# STM32_F407.net
KiCad netlist of a schematic drawn in Altium Designer
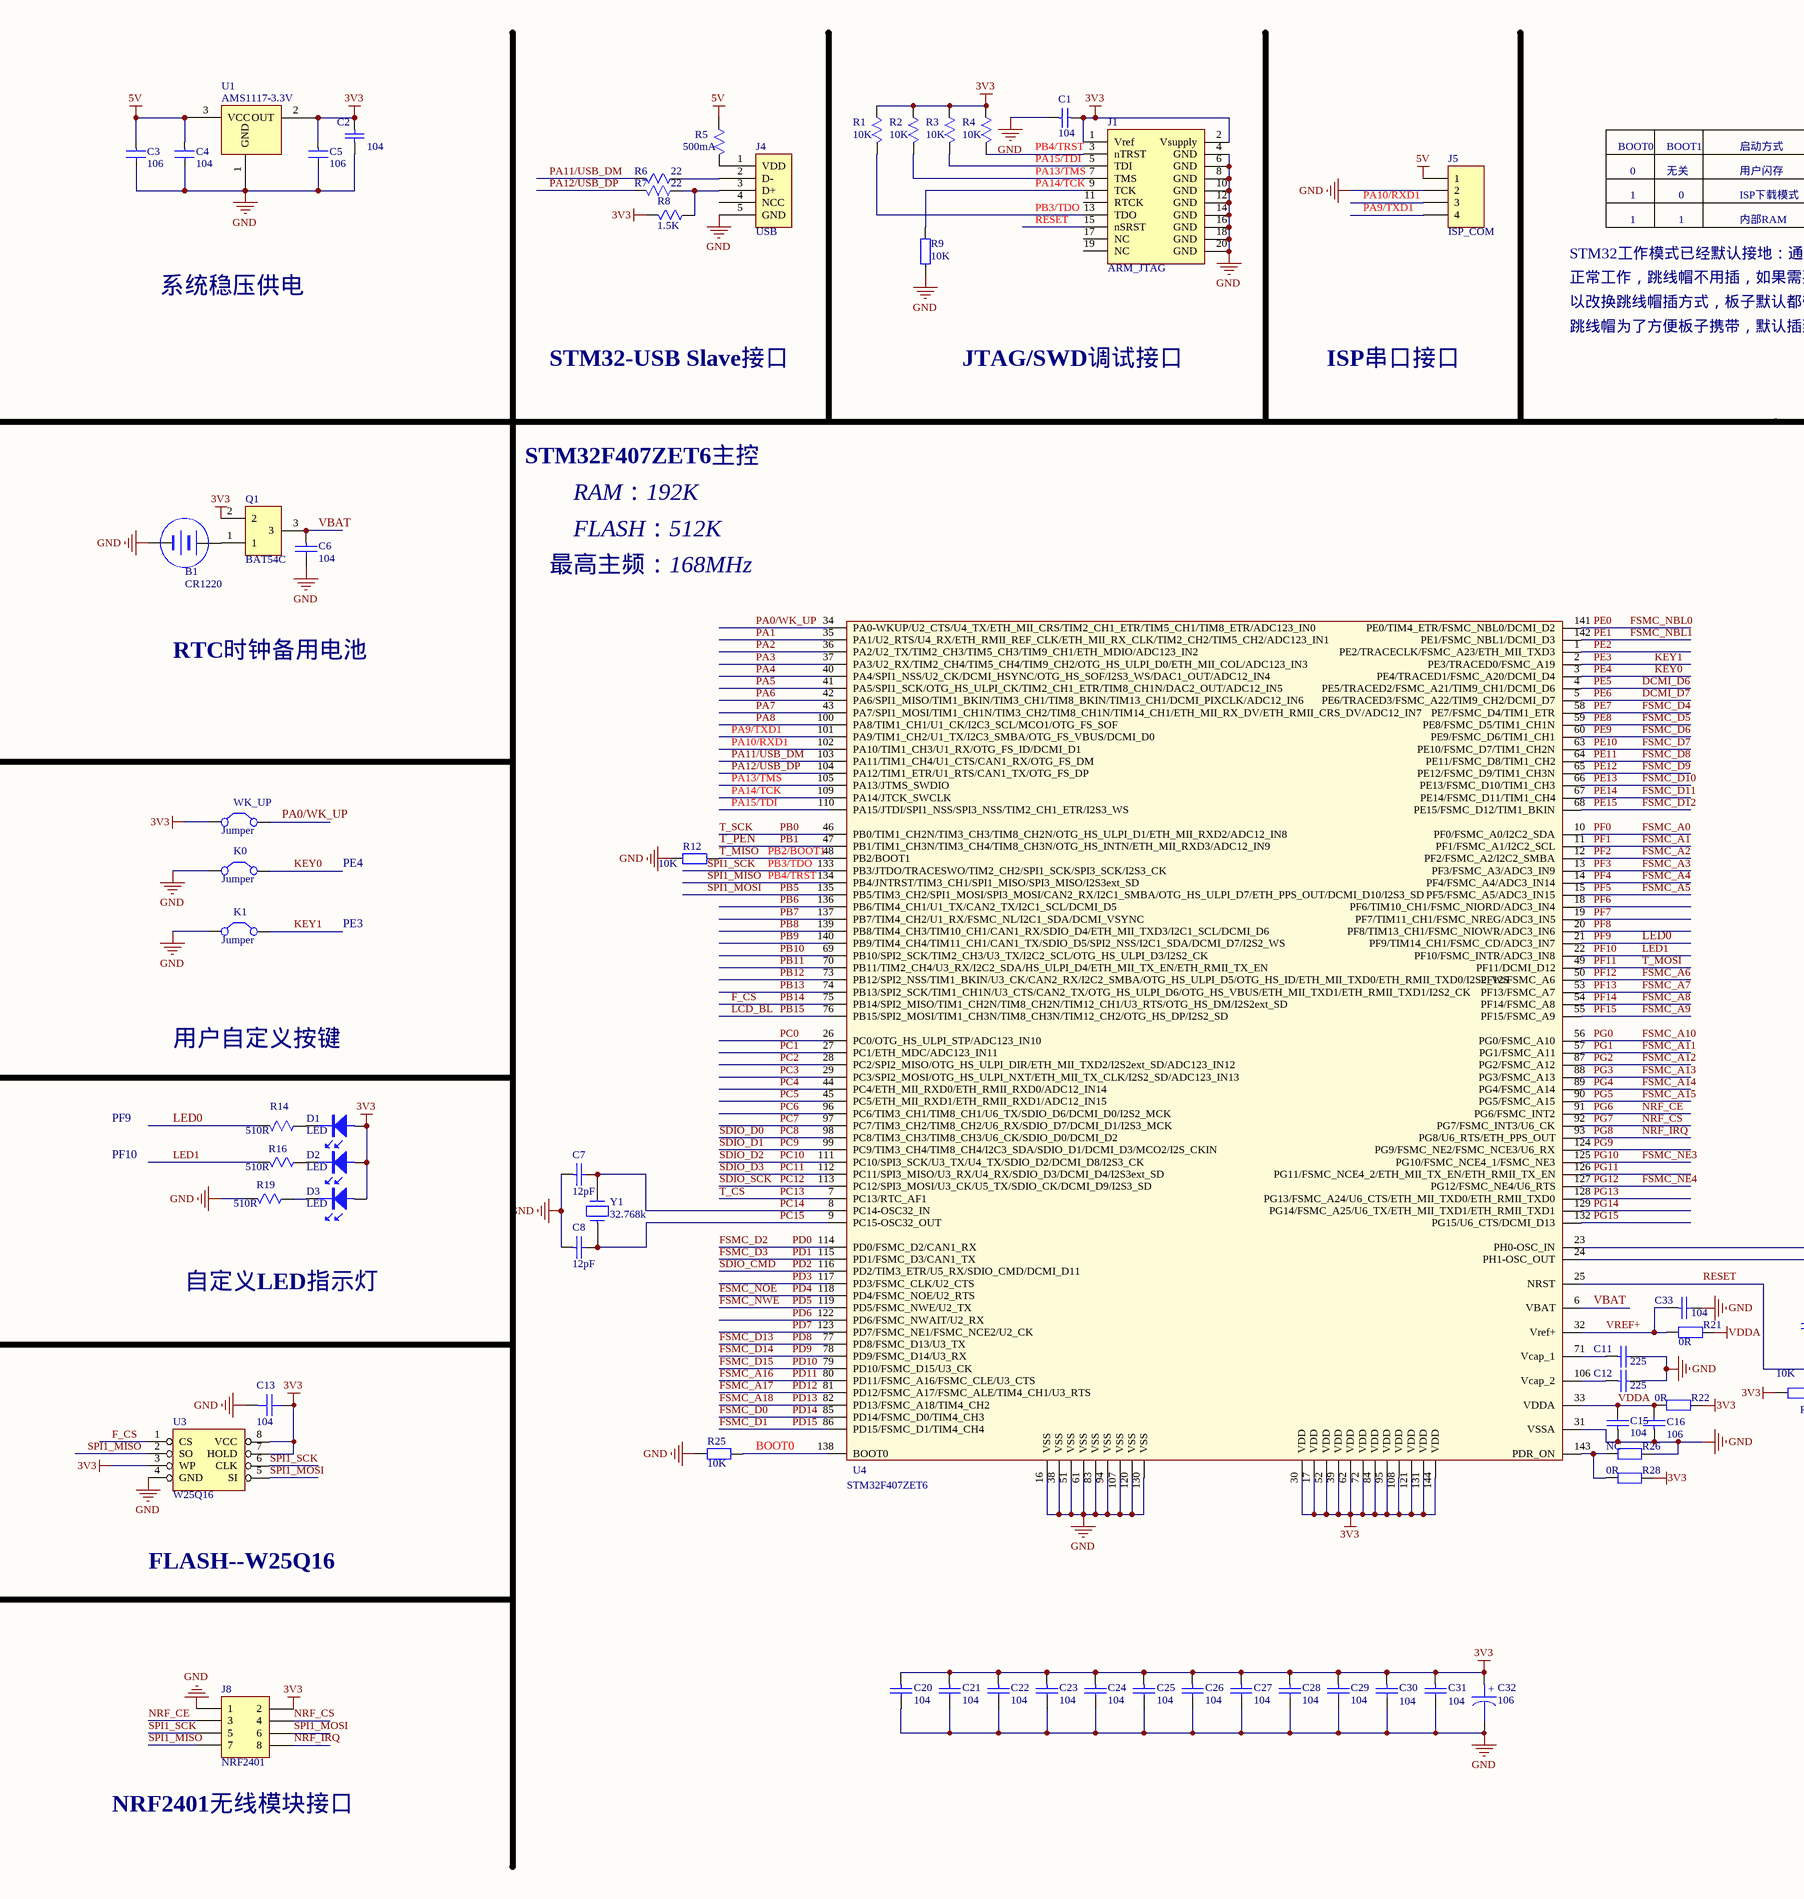
[diagram p0: STM32_F407.SchDoc, left]
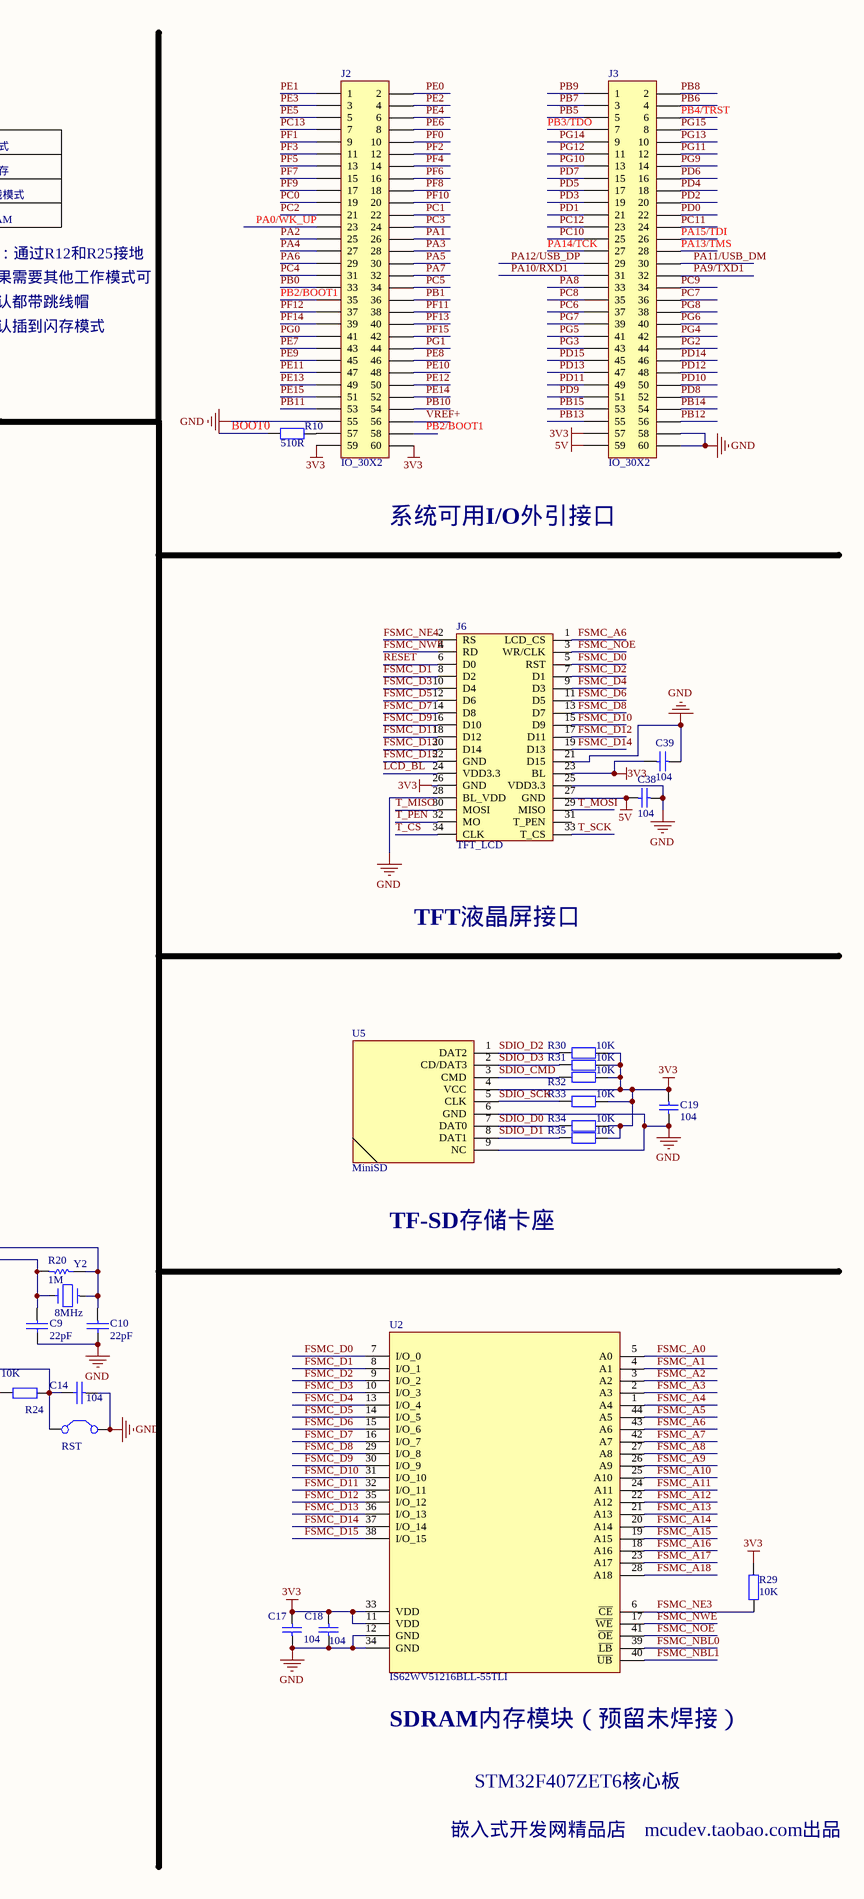
[diagram p1: STM32_F407.SchDoc, right]

(export (version "E")
  (design (tool "Eeschema 10.0.6"))
  (components
    (comp (ref "B1") (value "CR1220") (footprint "CP1220") (libsource (lib "YT1_SCH_99SE") (part "BATTERY")))
    (comp (ref "C1")
      (value "104")
      (footprint "RC0603")
      (description "Capacitor")
      (fields (field (name "PUBLISHER") "Altium Limited"))
      (libsource (lib "*") (part "Cap"))
    )
    (comp (ref "C2")
      (value "104")
      (footprint "RC0603")
      (description "Capacitor")
      (fields (field (name "PUBLISHER") "Altium Limited"))
      (libsource (lib "*") (part "Cap"))
    )
    (comp (ref "C3")
      (value "106")
      (footprint "0805C")
      (description "Capacitor")
      (libsource (lib "电容") (part "0805C"))
    )
    (comp (ref "C4")
      (value "104")
      (footprint "0805C")
      (description "Capacitor")
      (libsource (lib "电容") (part "0805C"))
    )
    (comp (ref "C5")
      (value "106")
      (footprint "0805C")
      (description "Capacitor")
      (libsource (lib "电容") (part "0805C"))
    )
    (comp (ref "C6")
      (value "104")
      (footprint "RC0603")
      (description "Capcitor")
      (libsource (lib "") (part "CAP_1"))
    )
    (comp (ref "C7")
      (value "12pF")
      (footprint "0603C")
      (description "Capcitor")
      (libsource (lib "LXKJSJ") (part "CAP"))
    )
    (comp (ref "C8")
      (value "12pF")
      (footprint "0603C")
      (description "Capcitor")
      (libsource (lib "LXKJSJ") (part "CAP"))
    )
    (comp (ref "C9")
      (value "22pF")
      (footprint "RC0603")
      (description "Capcitor")
      (libsource (lib "LXKJSJ") (part "CAP"))
    )
    (comp (ref "C10")
      (value "22pF")
      (footprint "RC0603")
      (description "Capcitor")
      (libsource (lib "LXKJSJ") (part "CAP"))
    )
    (comp (ref "C11")
      (value "225")
      (footprint "RC0805")
      (description "Capcitor")
      (libsource (lib "LXKJSJ") (part "CAP"))
    )
    (comp (ref "C12")
      (value "225")
      (footprint "RC0805")
      (description "Capcitor")
      (libsource (lib "LXKJSJ") (part "CAP"))
    )
    (comp (ref "C13") (value "104") (footprint "RC0603") (libsource (lib "YT1_SCH_99SE") (part "CAP")))
    (comp (ref "C14")
      (value "104")
      (footprint "RC0603")
      (description "Capcitor")
      (libsource (lib "LXKJSJ") (part "CAP"))
    )
    (comp (ref "C15")
      (value "104")
      (footprint "RC0603")
      (description "Capcitor")
      (libsource (lib "LXKJSJ") (part "CAP"))
    )
    (comp (ref "C16")
      (value "106")
      (footprint "RC0805")
      (description "Capcitor")
      (libsource (lib "LXKJSJ") (part "CAP"))
    )
    (comp (ref "C17")
      (value "104")
      (footprint "RC0603")
      (description "Capacitor")
      (fields (field (name "PUBLISHER") "Altium Limited"))
      (libsource (lib "*") (part "Cap"))
    )
    (comp (ref "C18")
      (value "104")
      (footprint "RC0603")
      (description "Capacitor")
      (fields (field (name "PUBLISHER") "Altium Limited"))
      (libsource (lib "*") (part "Cap"))
    )
    (comp (ref "C19")
      (value "104")
      (footprint "RC0603")
      (description "Capacitor (Semiconductor SIM Model)")
      (fields (field (name "PUBLISHER") "Altium Limited"))
      (libsource (lib "*") (part "Cap Semi"))
    )
    (comp (ref "C20")
      (value "104")
      (footprint "RC0603")
      (description "Capcitor")
      (libsource (lib "LXKJSJ") (part "CAP"))
    )
    (comp (ref "C21")
      (value "104")
      (footprint "RC0603")
      (description "Capcitor")
      (libsource (lib "LXKJSJ") (part "CAP"))
    )
    (comp (ref "C22")
      (value "104")
      (footprint "RC0603")
      (description "Capcitor")
      (libsource (lib "LXKJSJ") (part "CAP"))
    )
    (comp (ref "C23")
      (value "104")
      (footprint "RC0603")
      (description "Capcitor")
      (libsource (lib "LXKJSJ") (part "CAP"))
    )
    (comp (ref "C24")
      (value "104")
      (footprint "RC0603")
      (description "Capcitor")
      (libsource (lib "LXKJSJ") (part "CAP"))
    )
    (comp (ref "C25")
      (value "104")
      (footprint "RC0603")
      (description "Capcitor")
      (libsource (lib "LXKJSJ") (part "CAP"))
    )
    (comp (ref "C26")
      (value "104")
      (footprint "RC0603")
      (description "Capcitor")
      (libsource (lib "LXKJSJ") (part "CAP"))
    )
    (comp (ref "C27")
      (value "104")
      (footprint "RC0603")
      (description "Capcitor")
      (libsource (lib "LXKJSJ") (part "CAP"))
    )
    (comp (ref "C28")
      (value "104")
      (footprint "RC0603")
      (description "Capcitor")
      (libsource (lib "LXKJSJ") (part "CAP"))
    )
    (comp (ref "C29")
      (value "104")
      (footprint "RC0603")
      (description "Capcitor")
      (libsource (lib "LXKJSJ") (part "CAP"))
    )
    (comp (ref "C30")
      (value "104")
      (footprint "RC0603")
      (description "Capcitor")
      (libsource (lib "LXKJSJ") (part "CAP"))
    )
    (comp (ref "C31")
      (value "104")
      (footprint "RC0603")
      (description "Capcitor")
      (libsource (lib "LXKJSJ") (part "CAP"))
    )
    (comp (ref "C32")
      (value "106")
      (footprint "RC0805")
      (description "Capacitor")
      (libsource (lib "*") (part "CAPACITOR POL"))
    )
    (comp (ref "C33")
      (value "104")
      (footprint "RC0603")
      (description "Capcitor")
      (libsource (lib "LXKJSJ") (part "CAP"))
    )
    (comp (ref "C38")
      (value "104")
      (footprint "0603C")
      (description "Capacitor")
      (fields (field (name "PUBLISHER") "Altium Limited"))
      (libsource (lib "*") (part "Cap"))
    )
    (comp (ref "C39")
      (value "104")
      (footprint "0603C")
      (description "Capacitor")
      (fields (field (name "PUBLISHER") "Altium Limited"))
      (libsource (lib "*") (part "Cap"))
    )
    (comp (ref "D1") (value "LED") (footprint "LED0805") (libsource (lib "*") (part "LED")))
    (comp (ref "D2") (value "LED") (footprint "LED0805") (libsource (lib "*") (part "LED")))
    (comp (ref "D3") (value "LED") (footprint "LED0805") (libsource (lib "*") (part "LED")))
    (comp (ref "J1")
      (value "ARM_JTAG")
      (footprint "JTAG20P")
      (description "JTAG")
      (libsource (lib "LXKJSJ") (part "JTAG"))
    )
    (comp (ref "J2")
      (value "IO_30X2")
      (footprint "IDE2X30")
      (description "Header, 30-Pin, Dual row")
      (fields (field (name "PUBLISHER") "Altium Limited"))
      (libsource (lib "Miscellaneous Connectors") (part "Header 30X2"))
    )
    (comp (ref "J3")
      (value "IO_30X2")
      (footprint "IDE2X30")
      (description "Header, 30-Pin, Dual row")
      (fields (field (name "PUBLISHER") "Altium Limited"))
      (libsource (lib "Miscellaneous Connectors") (part "Header 30X2"))
    )
    (comp (ref "J4") (value "USB") (footprint "MINUSB") (libsource (lib "YT1_SCH_99SE") (part "usb")))
    (comp (ref "J5")
      (value "ISP_COM")
      (footprint "HDR1X4")
      (description "Header, 4-Pin")
      (fields (field (name "PUBLISHER") "Altium Limited"))
      (libsource (lib "Miscellaneous Connectors") (part "Header 4"))
    )
    (comp (ref "J6") (value "TFT_LCD") (footprint "IDC34-Z") (libsource (lib "F4") (part "TFT_LCD")))
    (comp (ref "J8")
      (value "NRF2401")
      (footprint "DIP2X4-2.54")
      (description "Header, 4-Pin, Dual row")
      (fields (field (name "PUBLISHER") "Altium Limited"))
      (libsource (lib "Miscellaneous Connectors") (part "Header 4X2"))
    )
    (comp (ref "K0")
      (value "Jumper")
      (footprint "key")
      (description "Jumper Wire")
      (fields (field (name "PUBLISHER") "Altium Limited"))
      (libsource (lib "Free Documents") (part "Jumper"))
    )
    (comp (ref "K1")
      (value "Jumper")
      (footprint "key")
      (description "Jumper Wire")
      (fields (field (name "PUBLISHER") "Altium Limited"))
      (libsource (lib "Free Documents") (part "Jumper"))
    )
    (comp (ref "Q1") (value "BAT54C") (footprint "BAT54C") (libsource (lib "Newcapec9263") (part "BAT54C")))
    (comp (ref "R1") (value "10K") (footprint "RC0603") (libsource (lib "YT1_SCH_99SE") (part "RES")))
    (comp (ref "R2") (value "10K") (footprint "RC0603") (libsource (lib "YT1_SCH_99SE") (part "RES")))
    (comp (ref "R3") (value "10K") (footprint "RC0603") (libsource (lib "YT1_SCH_99SE") (part "RES")))
    (comp (ref "R4") (value "10K") (footprint "RC0603") (libsource (lib "YT1_SCH_99SE") (part "RES")))
    (comp (ref "R5") (value "500mA") (footprint "RC0805") (libsource (lib "YT1_SCH_99SE") (part "RES")))
    (comp (ref "R6") (value "22") (footprint "RC0603") (libsource (lib "YT1_SCH_99SE") (part "RES")))
    (comp (ref "R7") (value "22") (footprint "RC0603") (libsource (lib "YT1_SCH_99SE") (part "RES")))
    (comp (ref "R8") (value "1.5K") (footprint "RC0603") (libsource (lib "YT1_SCH_99SE") (part "RES")))
    (comp (ref "R9")
      (value "10K")
      (footprint "RC0603")
      (description "Resistor")
      (libsource (lib "Miscellaneous Devices") (part "Res2"))
    )
    (comp (ref "R10")
      (value "510R")
      (footprint "RC0603")
      (description "Resistor")
      (libsource (lib "") (part "Res2_2"))
    )
    (comp (ref "R12")
      (value "10K")
      (footprint "RC0603")
      (description "Resistor")
      (libsource (lib "") (part "Res2_2"))
    )
    (comp (ref "R14") (value "510R") (footprint "RC0603") (libsource (lib "YT1_SCH_99SE") (part "RES")))
    (comp (ref "R16") (value "510R") (footprint "RC0603") (libsource (lib "YT1_SCH_99SE") (part "RES")))
    (comp (ref "R19") (value "510R") (footprint "RC0603") (libsource (lib "YT1_SCH_99SE") (part "RES")))
    (comp (ref "R20")
      (value "1M")
      (footprint "RC0603")
      (description "Resistor")
      (libsource (lib "Miscellaneous Devices") (part "Res1"))
    )
    (comp (ref "R21")
      (value "0R")
      (footprint "RC0603")
      (description "Resistor")
      (libsource (lib "") (part "Res2_1"))
    )
    (comp (ref "R22")
      (value "0R")
      (footprint "RC0603")
      (description "Resistor")
      (libsource (lib "") (part "Res2_1"))
    )
    (comp (ref "R24")
      (value "10K")
      (footprint "RC0603")
      (description "Resistor")
      (libsource (lib "") (part "Res2_2"))
    )
    (comp (ref "R25")
      (value "10K")
      (footprint "RC0603")
      (description "Resistor")
      (libsource (lib "") (part "Res2_3"))
    )
    (comp (ref "R26")
      (value "NC")
      (footprint "RC0603")
      (description "Resistor")
      (libsource (lib "") (part "Res2_1"))
    )
    (comp (ref "R28")
      (value "0R")
      (footprint "RC0603")
      (description "Resistor")
      (libsource (lib "") (part "Res2_1"))
    )
    (comp (ref "R29")
      (value "10K")
      (footprint "RC0603")
      (description "Resistor")
      (libsource (lib "Miscellaneous Devices") (part "Res2"))
    )
    (comp (ref "R30")
      (value "10K")
      (footprint "RC0603")
      (description "Resistor")
      (libsource (lib "") (part "Res2_1"))
    )
    (comp (ref "R31")
      (value "10K")
      (footprint "RC0603")
      (description "Resistor")
      (libsource (lib "") (part "Res2_1"))
    )
    (comp (ref "R32")
      (value "10K")
      (footprint "RC0603")
      (description "Resistor")
      (libsource (lib "") (part "Res2_1"))
    )
    (comp (ref "R33")
      (value "10K")
      (footprint "RC0603")
      (description "Resistor")
      (libsource (lib "") (part "Res2_1"))
    )
    (comp (ref "R34")
      (value "10K")
      (footprint "RC0603")
      (description "Resistor")
      (libsource (lib "") (part "Res2_1"))
    )
    (comp (ref "R35")
      (value "10K")
      (footprint "RC0603")
      (description "Resistor")
      (libsource (lib "") (part "Res2_1"))
    )
    (comp (ref "RST")
      (value "Key")
      (footprint "key")
      (description "Jumper Wire")
      (fields (field (name "PUBLISHER") "Altium Limited"))
      (libsource (lib "Free Documents") (part "Jumper"))
    )
    (comp (ref "U1") (value "AMS1117-3.3V") (footprint "SOT223") (libsource (lib "*") (part "11")))
    (comp (ref "U2")
      (value "IS62WV51216BLL-55TLI")
      (footprint "TSOP44")
      (libsource (lib "STM32_DSO") (part "IS62WV51216BLL-55TLI"))
    )
    (comp (ref "U3") (value "W25Q16") (footprint "SOIC8P") (libsource (lib "YT1_SCH_99SE") (part "W25X16")))
    (comp (ref "U4")
      (value "STM32F407ZET6")
      (footprint "LQFP144N")
      (libsource (lib "EXPLORER") (part "STM32F407ZET6"))
    )
    (comp (ref "U5") (value "MiniSD") (footprint "TF_SD") (libsource (lib "STM32_RF") (part "MiniSD")))
    (comp (ref "WK_UP")
      (value "Jumper")
      (footprint "key")
      (description "Jumper Wire")
      (fields (field (name "PUBLISHER") "Altium Limited"))
      (libsource (lib "Free Documents") (part "Jumper"))
    )
    (comp (ref "Y1")
      (value "32.768k")
      (footprint "XTAL_2X6")
      (description "Crystal 8MHz PLUG")
      (libsource (lib "*") (part "CRYSTAL"))
    )
    (comp (ref "Y2")
      (value "8MHz")
      (footprint "X5032")
      (description "Crystal Oscillator")
      (libsource (lib "LXKJSJ") (part "XTAL"))
    )
  )
  (nets
    (net (code "2") (name "/BOOT0") (class "Default")
      (node (ref "R10") (pin "2") (pinfunction "2_2") (pintype "passive"))
      (node (ref "R25") (pin "1") (pinfunction "1_1") (pintype "passive"))
      (node (ref "U4") (pin "138") (pinfunction "BOOT0_138") (pintype "passive"))
    )
    (net (code "3") (name "/DCMI_D6") (class "Default")
      (node (ref "J2") (pin "5") (pinfunction "5_5") (pintype "passive"))
      (node (ref "U4") (pin "4") (pinfunction "PE5/TRACED2/FSMC_A21/TIM9_CH1/DCMI_D6_4") (pintype "passive"))
    )
    (net (code "4") (name "/DCMI_D7") (class "Default")
      (node (ref "J2") (pin "8") (pinfunction "8_8") (pintype "passive"))
      (node (ref "U4") (pin "5") (pinfunction "PE6/TRACED3/FSMC_A22/TIM9_CH2/DCMI_D7_5") (pintype "passive"))
    )
    (net (code "5") (name "/FSMC_A0") (class "Default")
      (node (ref "J2") (pin "10") (pinfunction "10_10") (pintype "passive"))
      (node (ref "U2") (pin "5") (pinfunction "A0_5") (pintype "passive"))
      (node (ref "U4") (pin "10") (pinfunction "PF0/FSMC_A0/I2C2_SDA_10") (pintype "passive"))
    )
    (net (code "6") (name "/FSMC_A1") (class "Default")
      (node (ref "J2") (pin "9") (pinfunction "9_9") (pintype "passive"))
      (node (ref "U2") (pin "4") (pinfunction "A1_4") (pintype "passive"))
      (node (ref "U4") (pin "11") (pinfunction "PF1/FSMC_A1/I2C2_SCL_11") (pintype "passive"))
    )
    (net (code "7") (name "/FSMC_A2") (class "Default")
      (node (ref "J2") (pin "12") (pinfunction "12_12") (pintype "passive"))
      (node (ref "U2") (pin "3") (pinfunction "A2_3") (pintype "passive"))
      (node (ref "U4") (pin "12") (pinfunction "PF2/FSMC_A2/I2C2_SMBA_12") (pintype "passive"))
    )
    (net (code "8") (name "/FSMC_A3") (class "Default")
      (node (ref "J2") (pin "11") (pinfunction "11_11") (pintype "passive"))
      (node (ref "U2") (pin "2") (pinfunction "A3_2") (pintype "passive"))
      (node (ref "U4") (pin "13") (pinfunction "PF3/FSMC_A3/ADC3_IN9_13") (pintype "passive"))
    )
    (net (code "9") (name "/FSMC_A4") (class "Default")
      (node (ref "J2") (pin "14") (pinfunction "14_14") (pintype "passive"))
      (node (ref "U2") (pin "1") (pinfunction "A4_1") (pintype "passive"))
      (node (ref "U4") (pin "14") (pinfunction "PF4/FSMC_A4/ADC3_IN14_14") (pintype "passive"))
    )
    (net (code "10") (name "/FSMC_A5") (class "Default")
      (node (ref "J2") (pin "13") (pinfunction "13_13") (pintype "passive"))
      (node (ref "U2") (pin "44") (pinfunction "A5_44") (pintype "passive"))
      (node (ref "U4") (pin "15") (pinfunction "PF5/FSMC_A5/ADC3_IN15_15") (pintype "passive"))
    )
    (net (code "11") (name "/FSMC_A6") (class "Default")
      (node (ref "J2") (pin "37") (pinfunction "37_37") (pintype "passive"))
      (node (ref "J6") (pin "1") (pinfunction "LCD_CS_1") (pintype "passive"))
      (node (ref "U2") (pin "43") (pinfunction "A6_43") (pintype "passive"))
      (node (ref "U4") (pin "50") (pinfunction "PF12/FSMC_A6_50") (pintype "passive"))
    )
    (net (code "12") (name "/FSMC_A7") (class "Default")
      (node (ref "J2") (pin "40") (pinfunction "40_40") (pintype "passive"))
      (node (ref "U2") (pin "42") (pinfunction "A7_42") (pintype "passive"))
      (node (ref "U4") (pin "53") (pinfunction "PF13/FSMC_A7_53") (pintype "passive"))
    )
    (net (code "13") (name "/FSMC_A8") (class "Default")
      (node (ref "J2") (pin "39") (pinfunction "39_39") (pintype "passive"))
      (node (ref "U2") (pin "27") (pinfunction "A8_27") (pintype "passive"))
      (node (ref "U4") (pin "54") (pinfunction "PF14/FSMC_A8_54") (pintype "passive"))
    )
    (net (code "14") (name "/FSMC_A9") (class "Default")
      (node (ref "J2") (pin "42") (pinfunction "42_42") (pintype "passive"))
      (node (ref "U2") (pin "26") (pinfunction "A9_26") (pintype "passive"))
      (node (ref "U4") (pin "55") (pinfunction "PF15/FSMC_A9_55") (pintype "passive"))
    )
    (net (code "15") (name "/FSMC_A10") (class "Default")
      (node (ref "J2") (pin "41") (pinfunction "41_41") (pintype "passive"))
      (node (ref "U2") (pin "25") (pinfunction "A10_25") (pintype "passive"))
      (node (ref "U4") (pin "56") (pinfunction "PG0/FSMC_A10_56") (pintype "passive"))
    )
    (net (code "16") (name "/FSMC_A11") (class "Default")
      (node (ref "J2") (pin "44") (pinfunction "44_44") (pintype "passive"))
      (node (ref "U2") (pin "24") (pinfunction "A11_24") (pintype "passive"))
      (node (ref "U4") (pin "57") (pinfunction "PG1/FSMC_A11_57") (pintype "passive"))
    )
    (net (code "17") (name "/FSMC_A12") (class "Default")
      (node (ref "J3") (pin "44") (pinfunction "44_44") (pintype "passive"))
      (node (ref "U2") (pin "22") (pinfunction "A12_22") (pintype "passive"))
      (node (ref "U4") (pin "87") (pinfunction "PG2/FSMC_A12_87") (pintype "passive"))
    )
    (net (code "18") (name "/FSMC_A13") (class "Default")
      (node (ref "J3") (pin "43") (pinfunction "43_43") (pintype "passive"))
      (node (ref "U2") (pin "21") (pinfunction "A13_21") (pintype "passive"))
      (node (ref "U4") (pin "88") (pinfunction "PG3/FSMC_A13_88") (pintype "passive"))
    )
    (net (code "19") (name "/FSMC_A14") (class "Default")
      (node (ref "J3") (pin "42") (pinfunction "42_42") (pintype "passive"))
      (node (ref "U2") (pin "20") (pinfunction "A14_20") (pintype "passive"))
      (node (ref "U4") (pin "89") (pinfunction "PG4/FSMC_A14_89") (pintype "passive"))
    )
    (net (code "20") (name "/FSMC_A15") (class "Default")
      (node (ref "J3") (pin "41") (pinfunction "41_41") (pintype "passive"))
      (node (ref "U2") (pin "19") (pinfunction "A15_19") (pintype "passive"))
      (node (ref "U4") (pin "90") (pinfunction "PG5/FSMC_A15_90") (pintype "passive"))
    )
    (net (code "21") (name "/FSMC_A16") (class "Default")
      (node (ref "J3") (pin "49") (pinfunction "49_49") (pintype "passive"))
      (node (ref "U2") (pin "18") (pinfunction "A16_18") (pintype "passive"))
      (node (ref "U4") (pin "80") (pinfunction "PD11/FSMC_A16/FSMC_CLE/U3_CTS_80") (pintype "passive"))
    )
    (net (code "22") (name "/FSMC_A17") (class "Default")
      (node (ref "J3") (pin "48") (pinfunction "48_48") (pintype "passive"))
      (node (ref "U2") (pin "23") (pinfunction "A17_23") (pintype "passive"))
      (node (ref "U4") (pin "81") (pinfunction "PD12/FSMC_A17/FSMC_ALE/TIM4_CH1/U3_RTS_81") (pintype "passive"))
    )
    (net (code "23") (name "/FSMC_A18") (class "Default")
      (node (ref "J3") (pin "47") (pinfunction "47_47") (pintype "passive"))
      (node (ref "U2") (pin "28") (pinfunction "A18_28") (pintype "passive"))
      (node (ref "U4") (pin "82") (pinfunction "PD13/FSMC_A18/TIM4_CH2_82") (pintype "passive"))
    )
    (net (code "24") (name "/FSMC_D0") (class "Default")
      (node (ref "J3") (pin "46") (pinfunction "46_46") (pintype "passive"))
      (node (ref "J6") (pin "5") (pinfunction "RST_5") (pintype "passive"))
      (node (ref "U2") (pin "7") (pinfunction "I/O_0_7") (pintype "passive"))
      (node (ref "U4") (pin "85") (pinfunction "PD14/FSMC_D0/TIM4_CH3_85") (pintype "passive"))
    )
    (net (code "25") (name "/FSMC_D1") (class "Default")
      (node (ref "J3") (pin "45") (pinfunction "45_45") (pintype "passive"))
      (node (ref "J6") (pin "8") (pinfunction "D2_8") (pintype "passive"))
      (node (ref "U2") (pin "8") (pinfunction "I/O_1_8") (pintype "passive"))
      (node (ref "U4") (pin "86") (pinfunction "PD15/FSMC_D1/TIM4_CH4_86") (pintype "passive"))
    )
    (net (code "26") (name "/FSMC_D2") (class "Default")
      (node (ref "J3") (pin "22") (pinfunction "22_22") (pintype "passive"))
      (node (ref "J6") (pin "7") (pinfunction "D1_7") (pintype "passive"))
      (node (ref "U2") (pin "9") (pinfunction "I/O_2_9") (pintype "passive"))
      (node (ref "U4") (pin "114") (pinfunction "PD0/FSMC_D2/CAN1_RX_114") (pintype "passive"))
    )
    (net (code "27") (name "/FSMC_D3") (class "Default")
      (node (ref "J3") (pin "21") (pinfunction "21_21") (pintype "passive"))
      (node (ref "J6") (pin "10") (pinfunction "D4_10") (pintype "passive"))
      (node (ref "U2") (pin "10") (pinfunction "I/O_3_10") (pintype "passive"))
      (node (ref "U4") (pin "115") (pinfunction "PD1/FSMC_D3/CAN1_TX_115") (pintype "passive"))
    )
    (net (code "28") (name "/FSMC_D4") (class "Default")
      (node (ref "J2") (pin "43") (pinfunction "43_43") (pintype "passive"))
      (node (ref "J6") (pin "9") (pinfunction "D3_9") (pintype "passive"))
      (node (ref "U2") (pin "13") (pinfunction "I/O_4_13") (pintype "passive"))
      (node (ref "U4") (pin "58") (pinfunction "PE7/FSMC_D4/TIM1_ETR_58") (pintype "passive"))
    )
    (net (code "29") (name "/FSMC_D5") (class "Default")
      (node (ref "J2") (pin "46") (pinfunction "46_46") (pintype "passive"))
      (node (ref "J6") (pin "12") (pinfunction "D6_12") (pintype "passive"))
      (node (ref "U2") (pin "14") (pinfunction "I/O_5_14") (pintype "passive"))
      (node (ref "U4") (pin "59") (pinfunction "PE8/FSMC_D5/TIM1_CH1N_59") (pintype "passive"))
    )
    (net (code "30") (name "/FSMC_D6") (class "Default")
      (node (ref "J2") (pin "45") (pinfunction "45_45") (pintype "passive"))
      (node (ref "J6") (pin "11") (pinfunction "D5_11") (pintype "passive"))
      (node (ref "U2") (pin "15") (pinfunction "I/O_6_15") (pintype "passive"))
      (node (ref "U4") (pin "60") (pinfunction "PE9/FSMC_D6/TIM1_CH1_60") (pintype "passive"))
    )
    (net (code "31") (name "/FSMC_D7") (class "Default")
      (node (ref "J2") (pin "48") (pinfunction "48_48") (pintype "passive"))
      (node (ref "J6") (pin "14") (pinfunction "D8_14") (pintype "passive"))
      (node (ref "U2") (pin "16") (pinfunction "I/O_7_16") (pintype "passive"))
      (node (ref "U4") (pin "63") (pinfunction "PE10/FSMC_D7/TIM1_CH2N_63") (pintype "passive"))
    )
    (net (code "32") (name "/FSMC_D8") (class "Default")
      (node (ref "J2") (pin "47") (pinfunction "47_47") (pintype "passive"))
      (node (ref "J6") (pin "13") (pinfunction "D7_13") (pintype "passive"))
      (node (ref "U2") (pin "29") (pinfunction "I/O_8_29") (pintype "passive"))
      (node (ref "U4") (pin "64") (pinfunction "PE11/FSMC_D8/TIM1_CH2_64") (pintype "passive"))
    )
    (net (code "33") (name "/FSMC_D9") (class "Default")
      (node (ref "J2") (pin "50") (pinfunction "50_50") (pintype "passive"))
      (node (ref "J6") (pin "16") (pinfunction "D10_16") (pintype "passive"))
      (node (ref "U2") (pin "30") (pinfunction "I/O_9_30") (pintype "passive"))
      (node (ref "U4") (pin "65") (pinfunction "PE12/FSMC_D9/TIM1_CH3N_65") (pintype "passive"))
    )
    (net (code "34") (name "/FSMC_D10") (class "Default")
      (node (ref "J2") (pin "49") (pinfunction "49_49") (pintype "passive"))
      (node (ref "J6") (pin "15") (pinfunction "D9_15") (pintype "passive"))
      (node (ref "U2") (pin "31") (pinfunction "I/O_10_31") (pintype "passive"))
      (node (ref "U4") (pin "66") (pinfunction "PE13/FSMC_D10/TIM1_CH3_66") (pintype "passive"))
    )
    (net (code "35") (name "/FSMC_D11") (class "Default")
      (node (ref "J2") (pin "52") (pinfunction "52_52") (pintype "passive"))
      (node (ref "J6") (pin "18") (pinfunction "D12_18") (pintype "passive"))
      (node (ref "U2") (pin "32") (pinfunction "I/O_11_32") (pintype "passive"))
      (node (ref "U4") (pin "67") (pinfunction "PE14/FSMC_D11/TIM1_CH4_67") (pintype "passive"))
    )
    (net (code "36") (name "/FSMC_D12") (class "Default")
      (node (ref "J2") (pin "51") (pinfunction "51_51") (pintype "passive"))
      (node (ref "J6") (pin "17") (pinfunction "D11_17") (pintype "passive"))
      (node (ref "U2") (pin "35") (pinfunction "I/O_12_35") (pintype "passive"))
      (node (ref "U4") (pin "68") (pinfunction "PE15/FSMC_D12/TIM1_BKIN_68") (pintype "passive"))
    )
    (net (code "37") (name "/FSMC_D13") (class "Default")
      (node (ref "J3") (pin "52") (pinfunction "52_52") (pintype "passive"))
      (node (ref "J6") (pin "20") (pinfunction "D14_20") (pintype "passive"))
      (node (ref "U2") (pin "36") (pinfunction "I/O_13_36") (pintype "passive"))
      (node (ref "U4") (pin "77") (pinfunction "PD8/FSMC_D13/U3_TX_77") (pintype "passive"))
    )
    (net (code "38") (name "/FSMC_D14") (class "Default")
      (node (ref "J3") (pin "51") (pinfunction "51_51") (pintype "passive"))
      (node (ref "J6") (pin "19") (pinfunction "D13_19") (pintype "passive"))
      (node (ref "U2") (pin "37") (pinfunction "I/O_14_37") (pintype "passive"))
      (node (ref "U4") (pin "78") (pinfunction "PD9/FSMC_D14/U3_RX_78") (pintype "passive"))
    )
    (net (code "39") (name "/FSMC_D15") (class "Default")
      (node (ref "J3") (pin "50") (pinfunction "50_50") (pintype "passive"))
      (node (ref "J6") (pin "22") (pinfunction "GND_22") (pintype "passive"))
      (node (ref "U2") (pin "38") (pinfunction "I/O_15_38") (pintype "passive"))
      (node (ref "U4") (pin "79") (pinfunction "PD10/FSMC_D15/U3_CK_79") (pintype "passive"))
    )
    (net (code "40") (name "/FSMC_NBL0") (class "Default")
      (node (ref "J2") (pin "2") (pinfunction "2_2") (pintype "passive"))
      (node (ref "U2") (pin "39") (pinfunction "~{LB}_39") (pintype "passive"))
      (node (ref "U4") (pin "141") (pinfunction "PE0/TIM4_ETR/FSMC_NBL0/DCMI_D2_141") (pintype "passive"))
    )
    (net (code "41") (name "/FSMC_NBL1") (class "Default")
      (node (ref "J2") (pin "1") (pinfunction "1_1") (pintype "passive"))
      (node (ref "U2") (pin "40") (pinfunction "~{UB}_40") (pintype "passive"))
      (node (ref "U4") (pin "142") (pinfunction "PE1/FSMC_NBL1/DCMI_D3_142") (pintype "passive"))
    )
    (net (code "42") (name "/FSMC_NE3") (class "Default")
      (node (ref "J3") (pin "13") (pinfunction "13_13") (pintype "passive"))
      (node (ref "R29") (pin "1") (pinfunction "1_1") (pintype "passive"))
      (node (ref "U2") (pin "6") (pinfunction "~{CE}_6") (pintype "passive"))
      (node (ref "U4") (pin "125") (pinfunction "PG10/FSMC_NCE4_1/FSMC_NE3_125") (pintype "passive"))
    )
    (net (code "43") (name "/FSMC_NE4") (class "Default")
      (node (ref "J3") (pin "11") (pinfunction "11_11") (pintype "passive"))
      (node (ref "J6") (pin "2") (pinfunction "RS_2") (pintype "passive"))
      (node (ref "U4") (pin "127") (pinfunction "PG12/FSMC_NE4/U6_RTS_127") (pintype "passive"))
    )
    (net (code "44") (name "/FSMC_NOE") (class "Default")
      (node (ref "J3") (pin "18") (pinfunction "18_18") (pintype "passive"))
      (node (ref "J6") (pin "3") (pinfunction "WR/CLK_3") (pintype "passive"))
      (node (ref "U2") (pin "41") (pinfunction "~{OE}_41") (pintype "passive"))
      (node (ref "U4") (pin "118") (pinfunction "PD4/FSMC_NOE/U2_RTS_118") (pintype "passive"))
    )
    (net (code "45") (name "/FSMC_NWE") (class "Default")
      (node (ref "J3") (pin "17") (pinfunction "17_17") (pintype "passive"))
      (node (ref "J6") (pin "4") (pinfunction "RD_4") (pintype "passive"))
      (node (ref "U2") (pin "17") (pinfunction "~{WE}_17") (pintype "passive"))
      (node (ref "U4") (pin "119") (pinfunction "PD5/FSMC_NWE/U2_TX_119") (pintype "passive"))
    )
    (net (code "46") (name "/F_CS") (class "Default")
      (node (ref "J3") (pin "54") (pinfunction "54_54") (pintype "passive"))
      (node (ref "U3") (pin "1") (pinfunction "CS_1") (pintype "passive"))
      (node (ref "U4") (pin "75") (pinfunction "PB14/SPI2_MISO/TIM1_CH2N/TIM8_CH2N/TIM12_CH1/U3_RTS/OTG_HS_DM/I2S2ext_SD_75") (pintype "passive"))
    )
    (net (code "47") (name "/KEY0") (class "Default")
      (node (ref "J2") (pin "6") (pinfunction "6_6") (pintype "passive"))
      (node (ref "K0") (pin "2") (pinfunction "C2_2") (pintype "passive"))
      (node (ref "U4") (pin "3") (pinfunction "PE4/TRACED1/FSMC_A20/DCMI_D4_3") (pintype "passive"))
    )
    (net (code "48") (name "/KEY1") (class "Default")
      (node (ref "J2") (pin "3") (pinfunction "3_3") (pintype "passive"))
      (node (ref "K1") (pin "2") (pinfunction "C2_2") (pintype "passive"))
      (node (ref "U4") (pin "2") (pinfunction "PE3/TRACED0/FSMC_A19_2") (pintype "passive"))
    )
    (net (code "49") (name "/LCD_BL") (class "Default")
      (node (ref "J3") (pin "53") (pinfunction "53_53") (pintype "passive"))
      (node (ref "J6") (pin "24") (pinfunction "VDD3.3_24") (pintype "passive"))
      (node (ref "U4") (pin "76") (pinfunction "PB15/SPI2_MOSI/TIM1_CH3N/TIM8_CH3N/TIM12_CH2/OTG_HS_DP/I2S2_SD_76") (pintype "passive"))
    )
    (net (code "50") (name "/LED0") (class "Default")
      (node (ref "J2") (pin "17") (pinfunction "17_17") (pintype "passive"))
      (node (ref "R14") (pin "2") (pinfunction "2_2") (pintype "passive"))
      (node (ref "U4") (pin "21") (pinfunction "PF9/TIM14_CH1/FSMC_CD/ADC3_IN7_21") (pintype "passive"))
    )
    (net (code "51") (name "/LED1") (class "Default")
      (node (ref "J2") (pin "20") (pinfunction "20_20") (pintype "passive"))
      (node (ref "R16") (pin "2") (pinfunction "2_2") (pintype "passive"))
      (node (ref "U4") (pin "22") (pinfunction "PF10/FSMC_INTR/ADC3_IN8_22") (pintype "passive"))
    )
    (net (code "52") (name "/NRF_CE") (class "Default")
      (node (ref "J3") (pin "40") (pinfunction "40_40") (pintype "passive"))
      (node (ref "J8") (pin "3") (pinfunction "3_3") (pintype "passive"))
      (node (ref "U4") (pin "91") (pinfunction "PG6/FSMC_INT2_91") (pintype "passive"))
    )
    (net (code "53") (name "/NRF_CS") (class "Default")
      (node (ref "J3") (pin "39") (pinfunction "39_39") (pintype "passive"))
      (node (ref "J8") (pin "4") (pinfunction "4_4") (pintype "passive"))
      (node (ref "U4") (pin "92") (pinfunction "PG7/FSMC_INT3/U6_CK_92") (pintype "passive"))
    )
    (net (code "54") (name "/NRF_IRQ") (class "Default")
      (node (ref "J3") (pin "38") (pinfunction "38_38") (pintype "passive"))
      (node (ref "J8") (pin "8") (pinfunction "8_8") (pintype "passive"))
      (node (ref "U4") (pin "93") (pinfunction "PG8/U6_RTS/ETH_PPS_OUT_93") (pintype "passive"))
    )
    (net (code "55") (name "/PA0{slash}WK_UP") (class "Default")
      (node (ref "J2") (pin "23") (pinfunction "23_23") (pintype "passive"))
      (node (ref "U4") (pin "34") (pinfunction "PA0-WKUP/U2_CTS/U4_TX/ETH_MII_CRS/TIM2_CH1_ETR/TIM5_CH1/TIM8_ETR/ADC123_IN0_34") (pintype "passive"))
      (node (ref "WK_UP") (pin "2") (pinfunction "C2_2") (pintype "passive"))
    )
    (net (code "56") (name "/PA1") (class "Default")
      (node (ref "J2") (pin "26") (pinfunction "26_26") (pintype "passive"))
      (node (ref "U4") (pin "35") (pinfunction "PA1/U2_RTS/U4_RX/ETH_RMII_REF_CLK/ETH_MII_RX_CLK/TIM2_CH2/TIM5_CH2/ADC123_IN1_35") (pintype "passive"))
    )
    (net (code "57") (name "/PA2") (class "Default")
      (node (ref "J2") (pin "25") (pinfunction "25_25") (pintype "passive"))
      (node (ref "U4") (pin "36") (pinfunction "PA2/U2_TX/TIM2_CH3/TIM5_CH3/TIM9_CH1/ETH_MDIO/ADC123_IN2_36") (pintype "passive"))
    )
    (net (code "58") (name "/PA3") (class "Default")
      (node (ref "J2") (pin "28") (pinfunction "28_28") (pintype "passive"))
      (node (ref "U4") (pin "37") (pinfunction "PA3/U2_RX/TIM2_CH4/TIM5_CH4/TIM9_CH2/OTG_HS_ULPI_D0/ETH_MII_COL/ADC123_IN3_37") (pintype "passive"))
    )
    (net (code "59") (name "/PA4") (class "Default")
      (node (ref "J2") (pin "27") (pinfunction "27_27") (pintype "passive"))
      (node (ref "U4") (pin "40") (pinfunction "PA4/SPI1_NSS/U2_CK/DCMI_HSYNC/OTG_HS_SOF/I2S3_WS/DAC1_OUT/ADC12_IN4_40") (pintype "passive"))
    )
    (net (code "60") (name "/PA5") (class "Default")
      (node (ref "J2") (pin "30") (pinfunction "30_30") (pintype "passive"))
      (node (ref "U4") (pin "41") (pinfunction "PA5/SPI1_SCK/OTG_HS_ULPI_CK/TIM2_CH1_ETR/TIM8_CH1N/DAC2_OUT/ADC12_IN5_41") (pintype "passive"))
    )
    (net (code "61") (name "/PA6") (class "Default")
      (node (ref "J2") (pin "29") (pinfunction "29_29") (pintype "passive"))
      (node (ref "U4") (pin "42") (pinfunction "PA6/SPI1_MISO/TIM1_BKIN/TIM3_CH1/TIM8_BKIN/TIM13_CH1/DCMI_PIXCLK/ADC12_IN6_42") (pintype "passive"))
    )
    (net (code "62") (name "/PA7") (class "Default")
      (node (ref "J2") (pin "32") (pinfunction "32_32") (pintype "passive"))
      (node (ref "U4") (pin "43") (pinfunction "PA7/SPI1_MOSI/TIM1_CH1N/TIM3_CH2/TIM8_CH1N/TIM14_CH1/ETH_MII_RX_DV/ETH_RMII_CRS_DV/ADC12_IN7_43") (pintype "passive"))
    )
    (net (code "63") (name "/PA8") (class "Default")
      (node (ref "J3") (pin "33") (pinfunction "33_33") (pintype "passive"))
      (node (ref "U4") (pin "100") (pinfunction "PA8/TIM1_CH1/U1_CK/I2C3_SCL/MCO1/OTG_FS_SOF_100") (pintype "passive"))
    )
    (net (code "64") (name "/PA9{slash}TXD1") (class "Default")
      (node (ref "J3") (pin "32") (pinfunction "32_32") (pintype "passive"))
      (node (ref "J5") (pin "4") (pinfunction "4_4") (pintype "passive"))
      (node (ref "U4") (pin "101") (pinfunction "PA9/TIM1_CH2/U1_TX/I2C3_SMBA/OTG_FS_VBUS/DCMI_D0_101") (pintype "passive"))
    )
    (net (code "65") (name "/PA10{slash}RXD1") (class "Default")
      (node (ref "J3") (pin "31") (pinfunction "31_31") (pintype "passive"))
      (node (ref "J5") (pin "3") (pinfunction "3_3") (pintype "passive"))
      (node (ref "U4") (pin "102") (pinfunction "PA10/TIM1_CH3/U1_RX/OTG_FS_ID/DCMI_D1_102") (pintype "passive"))
    )
    (net (code "66") (name "/PA11{slash}USB_DM") (class "Default")
      (node (ref "J3") (pin "30") (pinfunction "30_30") (pintype "passive"))
      (node (ref "R6") (pin "2") (pinfunction "2_2") (pintype "passive"))
      (node (ref "U4") (pin "103") (pinfunction "PA11/TIM1_CH4/U1_CTS/CAN1_RX/OTG_FS_DM_103") (pintype "passive"))
    )
    (net (code "67") (name "/PA12{slash}USB_DP") (class "Default")
      (node (ref "J3") (pin "29") (pinfunction "29_29") (pintype "passive"))
      (node (ref "R7") (pin "2") (pinfunction "2_2") (pintype "passive"))
      (node (ref "U4") (pin "104") (pinfunction "PA12/TIM1_ETR/U1_RTS/CAN1_TX/OTG_FS_DP_104") (pintype "passive"))
    )
    (net (code "68") (name "/PA13{slash}TMS") (class "Default")
      (node (ref "J1") (pin "7") (pinfunction "TMS_7") (pintype "passive"))
      (node (ref "J3") (pin "28") (pinfunction "28_28") (pintype "passive"))
      (node (ref "R2") (pin "2") (pinfunction "2_2") (pintype "passive"))
      (node (ref "U4") (pin "105") (pinfunction "PA13/JTMS_SWDIO_105") (pintype "passive"))
    )
    (net (code "69") (name "/PA14{slash}TCK") (class "Default")
      (node (ref "J1") (pin "9") (pinfunction "TCK_9") (pintype "passive"))
      (node (ref "J3") (pin "27") (pinfunction "27_27") (pintype "passive"))
      (node (ref "R9") (pin "2") (pinfunction "2_2") (pintype "passive"))
      (node (ref "U4") (pin "109") (pinfunction "PA14/JTCK_SWCLK_109") (pintype "passive"))
    )
    (net (code "70") (name "/PA15{slash}TDI") (class "Default")
      (node (ref "J1") (pin "5") (pinfunction "TDI_5") (pintype "passive"))
      (node (ref "J3") (pin "26") (pinfunction "26_26") (pintype "passive"))
      (node (ref "R3") (pin "2") (pinfunction "2_2") (pintype "passive"))
      (node (ref "U4") (pin "110") (pinfunction "PA15/JTDI/SPI1_NSS/SPI3_NSS/TIM2_CH1_ETR/I2S3_WS_110") (pintype "passive"))
    )
    (net (code "71") (name "/PB0") (class "Default")
      (node (ref "J2") (pin "33") (pinfunction "33_33") (pintype "passive"))
      (node (ref "J6") (pin "33") (pinfunction "T_CS_33") (pintype "passive"))
      (node (ref "U4") (pin "46") (pinfunction "PB0/TIM1_CH2N/TIM3_CH3/TIM8_CH2N/OTG_HS_ULPI_D1/ETH_MII_RXD2/ADC12_IN8_46") (pintype "passive"))
    )
    (net (code "72") (name "/PB1") (class "Default")
      (node (ref "J2") (pin "36") (pinfunction "36_36") (pintype "passive"))
      (node (ref "J6") (pin "32") (pinfunction "MO_32") (pintype "passive"))
      (node (ref "U4") (pin "47") (pinfunction "PB1/TIM1_CH3N/TIM3_CH4/TIM8_CH3N/OTG_HS_INTN/ETH_MII_RXD3/ADC12_IN9_47") (pintype "passive"))
    )
    (net (code "73") (name "/PB2{slash}BOOT1") (class "Default")
      (node (ref "J2") (pin "35") (pinfunction "35_35") (pintype "passive"))
      (node (ref "J2") (pin "58") (pinfunction "58_58") (pintype "passive"))
      (node (ref "J6") (pin "30") (pinfunction "MOSI_30") (pintype "passive"))
      (node (ref "R12") (pin "1") (pinfunction "1_1") (pintype "passive"))
      (node (ref "U4") (pin "48") (pinfunction "PB2/BOOT1_48") (pintype "passive"))
    )
    (net (code "74") (name "/PB3{slash}TDO") (class "Default")
      (node (ref "J1") (pin "13") (pinfunction "TDO_13") (pintype "passive"))
      (node (ref "J3") (pin "7") (pinfunction "7_7") (pintype "passive"))
      (node (ref "J8") (pin "5") (pinfunction "5_5") (pintype "passive"))
      (node (ref "R1") (pin "2") (pinfunction "2_2") (pintype "passive"))
      (node (ref "U3") (pin "6") (pinfunction "CLK_6") (pintype "passive"))
      (node (ref "U4") (pin "133") (pinfunction "PB3/JTDO/TRACESWO/TIM2_CH2/SPI1_SCK/SPI3_SCK/I2S3_CK_133") (pintype "passive"))
    )
    (net (code "75") (name "/PB4{slash}TRST") (class "Default")
      (node (ref "J1") (pin "3") (pinfunction "nTRST_3") (pintype "passive"))
      (node (ref "J3") (pin "6") (pinfunction "6_6") (pintype "passive"))
      (node (ref "J8") (pin "7") (pinfunction "7_7") (pintype "passive"))
      (node (ref "R4") (pin "2") (pinfunction "2_2") (pintype "passive"))
      (node (ref "U3") (pin "2") (pinfunction "SO_2") (pintype "passive"))
      (node (ref "U4") (pin "134") (pinfunction "PB4/JNTRST/TIM3_CH1/SPI1_MISO/SPI3_MISO/I2S3ext_SD_134") (pintype "passive"))
    )
    (net (code "76") (name "/PB5") (class "Default")
      (node (ref "J3") (pin "5") (pinfunction "5_5") (pintype "passive"))
      (node (ref "J8") (pin "6") (pinfunction "6_6") (pintype "passive"))
      (node (ref "U3") (pin "5") (pinfunction "SI_5") (pintype "passive"))
      (node (ref "U4") (pin "135") (pinfunction "PB5/TIM3_CH2/SPI1_MOSI/SPI3_MOSI/CAN2_RX/I2C1_SMBA/OTG_HS_ULPI_D7/ETH_PPS_OUT/DCMI_D10/I2S3_SD_135") (pintype "passive"))
    )
    (net (code "77") (name "/PB6") (class "Default")
      (node (ref "J3") (pin "4") (pinfunction "4_4") (pintype "passive"))
      (node (ref "U4") (pin "136") (pinfunction "PB6/TIM4_CH1/U1_TX/CAN2_TX/I2C1_SCL/DCMI_D5_136") (pintype "passive"))
    )
    (net (code "78") (name "/PB7") (class "Default")
      (node (ref "J3") (pin "3") (pinfunction "3_3") (pintype "passive"))
      (node (ref "U4") (pin "137") (pinfunction "PB7/TIM4_CH2/U1_RX/FSMC_NL/I2C1_SDA/DCMI_VSYNC_137") (pintype "passive"))
    )
    (net (code "79") (name "/PB8") (class "Default")
      (node (ref "J3") (pin "2") (pinfunction "2_2") (pintype "passive"))
      (node (ref "U4") (pin "139") (pinfunction "PB8/TIM4_CH3/TIM10_CH1/CAN1_RX/SDIO_D4/ETH_MII_TXD3/I2C1_SCL/DCMI_D6_139") (pintype "passive"))
    )
    (net (code "80") (name "/PB9") (class "Default")
      (node (ref "J3") (pin "1") (pinfunction "1_1") (pintype "passive"))
      (node (ref "U4") (pin "140") (pinfunction "PB9/TIM4_CH4/TIM11_CH1/CAN1_TX/SDIO_D5/SPI2_NSS/I2C1_SDA/DCMI_D7/I2S2_WS_140") (pintype "passive"))
    )
    (net (code "81") (name "/PB10") (class "Default")
      (node (ref "J2") (pin "54") (pinfunction "54_54") (pintype "passive"))
      (node (ref "U4") (pin "69") (pinfunction "PB10/SPI2_SCK/TIM2_CH3/U3_TX/I2C2_SCL/OTG_HS_ULPI_D3/I2S2_CK_69") (pintype "passive"))
    )
    (net (code "82") (name "/PB11") (class "Default")
      (node (ref "J2") (pin "53") (pinfunction "53_53") (pintype "passive"))
      (node (ref "U4") (pin "70") (pinfunction "PB11/TIM2_CH4/U3_RX/I2C2_SDA/HS_ULPI_D4/ETH_MII_TX_EN/ETH_RMII_TX_EN_70") (pintype "passive"))
    )
    (net (code "83") (name "/PB12") (class "Default")
      (node (ref "J3") (pin "56") (pinfunction "56_56") (pintype "passive"))
      (node (ref "U4") (pin "73") (pinfunction "PB12/SPI2_NSS/TIM1_BKIN/U3_CK/CAN2_RX/I2C2_SMBA/OTG_HS_ULPI_D5/OTG_HS_ID/ETH_MII_TXD0/ETH_RMII_TXD0/I2S2_WS_73") (pintype "passive"))
    )
    (net (code "84") (name "/PB13") (class "Default")
      (node (ref "J3") (pin "55") (pinfunction "55_55") (pintype "passive"))
      (node (ref "U4") (pin "74") (pinfunction "PB13/SPI2_SCK/TIM1_CH1N/U3_CTS/CAN2_TX/OTG_HS_ULPI_D6/OTG_HS_VBUS/ETH_MII_TXD1/ETH_RMII_TXD1/I2S2_CK_74") (pintype "passive"))
    )
    (net (code "85") (name "/PC0") (class "Default")
      (node (ref "J2") (pin "19") (pinfunction "19_19") (pintype "passive"))
      (node (ref "U4") (pin "26") (pinfunction "PC0/OTG_HS_ULPI_STP/ADC123_IN10_26") (pintype "passive"))
    )
    (net (code "86") (name "/PC1") (class "Default")
      (node (ref "J2") (pin "22") (pinfunction "22_22") (pintype "passive"))
      (node (ref "U4") (pin "27") (pinfunction "PC1/ETH_MDC/ADC123_IN11_27") (pintype "passive"))
    )
    (net (code "87") (name "/PC2") (class "Default")
      (node (ref "J2") (pin "21") (pinfunction "21_21") (pintype "passive"))
      (node (ref "U4") (pin "28") (pinfunction "PC2/SPI2_MISO/OTG_HS_ULPI_DIR/ETH_MII_TXD2/I2S2ext_SD/ADC123_IN12_28") (pintype "passive"))
    )
    (net (code "88") (name "/PC3") (class "Default")
      (node (ref "J2") (pin "24") (pinfunction "24_24") (pintype "passive"))
      (node (ref "U4") (pin "29") (pinfunction "PC3/SPI2_MOSI/OTG_HS_ULPI_NXT/ETH_MII_TX_CLK/I2S2_SD/ADC123_IN13_29") (pintype "passive"))
    )
    (net (code "89") (name "/PC4") (class "Default")
      (node (ref "J2") (pin "31") (pinfunction "31_31") (pintype "passive"))
      (node (ref "U4") (pin "44") (pinfunction "PC4/ETH_MII_RXD0/ETH_RMII_RXD0/ADC12_IN14_44") (pintype "passive"))
    )
    (net (code "90") (name "/PC5") (class "Default")
      (node (ref "J2") (pin "34") (pinfunction "34_34") (pintype "passive"))
      (node (ref "U4") (pin "45") (pinfunction "PC5/ETH_MII_RXD1/ETH_RMII_RXD1/ADC12_IN15_45") (pintype "passive"))
    )
    (net (code "91") (name "/PC6") (class "Default")
      (node (ref "J3") (pin "37") (pinfunction "37_37") (pintype "passive"))
      (node (ref "U4") (pin "96") (pinfunction "PC6/TIM3_CH1/TIM8_CH1/U6_TX/SDIO_D6/DCMI_D0/I2S2_MCK_96") (pintype "passive"))
    )
    (net (code "92") (name "/PC7") (class "Default")
      (node (ref "J3") (pin "36") (pinfunction "36_36") (pintype "passive"))
      (node (ref "U4") (pin "97") (pinfunction "PC7/TIM3_CH2/TIM8_CH2/U6_RX/SDIO_D7/DCMI_D1/I2S3_MCK_97") (pintype "passive"))
    )
    (net (code "93") (name "/PC8") (class "Default")
      (node (ref "J3") (pin "35") (pinfunction "35_35") (pintype "passive"))
      (node (ref "R34") (pin "1") (pinfunction "1_1") (pintype "passive"))
      (node (ref "U4") (pin "98") (pinfunction "PC8/TIM3_CH3/TIM8_CH3/U6_CK/SDIO_D0/DCMI_D2_98") (pintype "passive"))
      (node (ref "U5") (pin "7") (pinfunction "DAT0_7") (pintype "passive"))
    )
    (net (code "94") (name "/PC9") (class "Default")
      (node (ref "J3") (pin "34") (pinfunction "34_34") (pintype "passive"))
      (node (ref "R35") (pin "1") (pinfunction "1_1") (pintype "passive"))
      (node (ref "U4") (pin "99") (pinfunction "PC9/TIM3_CH4/TIM8_CH4/I2C3_SDA/SDIO_D1/DCMI_D3/MCO2/I2S_CKIN_99") (pintype "passive"))
      (node (ref "U5") (pin "8") (pinfunction "DAT1_8") (pintype "passive"))
    )
    (net (code "95") (name "/PC10") (class "Default")
      (node (ref "J3") (pin "25") (pinfunction "25_25") (pintype "passive"))
      (node (ref "R30") (pin "1") (pinfunction "1_1") (pintype "passive"))
      (node (ref "U4") (pin "111") (pinfunction "PC10/SPI3_SCK/U3_TX/U4_TX/SDIO_D2/DCMI_D8/I2S3_CK_111") (pintype "passive"))
      (node (ref "U5") (pin "1") (pinfunction "DAT2_1") (pintype "passive"))
    )
    (net (code "96") (name "/PC11") (class "Default")
      (node (ref "J3") (pin "24") (pinfunction "24_24") (pintype "passive"))
      (node (ref "R31") (pin "1") (pinfunction "1_1") (pintype "passive"))
      (node (ref "U4") (pin "112") (pinfunction "PC11/SPI3_MISO/U3_RX/U4_RX/SDIO_D3/DCMI_D4/I2S3ext_SD_112") (pintype "passive"))
      (node (ref "U5") (pin "2") (pinfunction "CD/DAT3_2") (pintype "passive"))
    )
    (net (code "97") (name "/PC12") (class "Default")
      (node (ref "J3") (pin "23") (pinfunction "23_23") (pintype "passive"))
      (node (ref "R33") (pin "1") (pinfunction "1_1") (pintype "passive"))
      (node (ref "U4") (pin "113") (pinfunction "PC12/SPI3_MOSI/U3_CK/U5_TX/SDIO_CK/DCMI_D9/I2S3_SD_113") (pintype "passive"))
      (node (ref "U5") (pin "5") (pinfunction "CLK_5") (pintype "passive"))
    )
    (net (code "98") (name "/PC13") (class "Default")
      (node (ref "J2") (pin "7") (pinfunction "7_7") (pintype "passive"))
      (node (ref "J6") (pin "34") (pinfunction "CLK_34") (pintype "passive"))
      (node (ref "U4") (pin "7") (pinfunction "PC13/RTC_AF1_7") (pintype "passive"))
    )
    (net (code "99") (name "/PC14") (class "Default")
      (node (ref "C7") (pin "2") (pinfunction "2_2") (pintype "passive"))
      (node (ref "U4") (pin "8") (pinfunction "PC14-OSC32_IN_8") (pintype "passive"))
      (node (ref "Y1") (pin "2") (pinfunction "2_2") (pintype "passive"))
    )
    (net (code "100") (name "/PC15") (class "Default")
      (node (ref "C8") (pin "2") (pinfunction "2_2") (pintype "passive"))
      (node (ref "U4") (pin "9") (pinfunction "PC15-OSC32_OUT_9") (pintype "passive"))
      (node (ref "Y1") (pin "1") (pinfunction "1_1") (pintype "passive"))
    )
    (net (code "101") (name "/PD2") (class "Default")
      (node (ref "J3") (pin "20") (pinfunction "20_20") (pintype "passive"))
      (node (ref "R32") (pin "1") (pinfunction "1_1") (pintype "passive"))
      (node (ref "U4") (pin "116") (pinfunction "PD2/TIM3_ETR/U5_RX/SDIO_CMD/DCMI_D11_116") (pintype "passive"))
      (node (ref "U5") (pin "3") (pinfunction "CMD_3") (pintype "passive"))
    )
    (net (code "102") (name "/PD3") (class "Default")
      (node (ref "J3") (pin "19") (pinfunction "19_19") (pintype "passive"))
      (node (ref "U4") (pin "117") (pinfunction "PD3/FSMC_CLK/U2_CTS_117") (pintype "passive"))
    )
    (net (code "103") (name "/PD6") (class "Default")
      (node (ref "J3") (pin "16") (pinfunction "16_16") (pintype "passive"))
      (node (ref "U4") (pin "122") (pinfunction "PD6/FSMC_NWAIT/U2_RX_122") (pintype "passive"))
    )
    (net (code "104") (name "/PD7") (class "Default")
      (node (ref "J3") (pin "15") (pinfunction "15_15") (pintype "passive"))
      (node (ref "U4") (pin "123") (pinfunction "PD7/FSMC_NE1/FSMC_NCE2/U2_CK_123") (pintype "passive"))
    )
    (net (code "105") (name "/PE2") (class "Default")
      (node (ref "J2") (pin "4") (pinfunction "4_4") (pintype "passive"))
      (node (ref "U4") (pin "1") (pinfunction "PE2/TRACECLK/FSMC_A23/ETH_MII_TXD3_1") (pintype "passive"))
    )
    (net (code "106") (name "/PF6") (class "Default")
      (node (ref "J2") (pin "16") (pinfunction "16_16") (pintype "passive"))
      (node (ref "U4") (pin "18") (pinfunction "PF6/TIM10_CH1/FSMC_NIORD/ADC3_IN4_18") (pintype "passive"))
    )
    (net (code "107") (name "/PF7") (class "Default")
      (node (ref "J2") (pin "15") (pinfunction "15_15") (pintype "passive"))
      (node (ref "U4") (pin "19") (pinfunction "PF7/TIM11_CH1/FSMC_NREG/ADC3_IN5_19") (pintype "passive"))
    )
    (net (code "108") (name "/PF8") (class "Default")
      (node (ref "J2") (pin "18") (pinfunction "18_18") (pintype "passive"))
      (node (ref "U4") (pin "20") (pinfunction "PF8/TIM13_CH1/FSMC_NIOWR/ADC3_IN6_20") (pintype "passive"))
    )
    (net (code "109") (name "/PF11") (class "Default")
      (node (ref "J2") (pin "38") (pinfunction "38_38") (pintype "passive"))
      (node (ref "J6") (pin "29") (pinfunction "MISO_29") (pintype "passive"))
      (node (ref "U4") (pin "49") (pinfunction "PF11/DCMI_D12_49") (pintype "passive"))
    )
    (net (code "110") (name "/PG9") (class "Default")
      (node (ref "J3") (pin "14") (pinfunction "14_14") (pintype "passive"))
      (node (ref "U4") (pin "124") (pinfunction "PG9/FSMC_NE2/FSMC_NCE3/U6_RX_124") (pintype "passive"))
    )
    (net (code "111") (name "/PG11") (class "Default")
      (node (ref "J3") (pin "12") (pinfunction "12_12") (pintype "passive"))
      (node (ref "U4") (pin "126") (pinfunction "PG11/FSMC_NCE4_2/ETH_MII_TX_EN/ETH_RMII_TX_EN_126") (pintype "passive"))
    )
    (net (code "112") (name "/PG13") (class "Default")
      (node (ref "J3") (pin "10") (pinfunction "10_10") (pintype "passive"))
      (node (ref "U4") (pin "128") (pinfunction "PG13/FSMC_A24/U6_CTS/ETH_MII_TXD0/ETH_RMII_TXD0_128") (pintype "passive"))
    )
    (net (code "113") (name "/PG14") (class "Default")
      (node (ref "J3") (pin "9") (pinfunction "9_9") (pintype "passive"))
      (node (ref "U4") (pin "129") (pinfunction "PG14/FSMC_A25/U6_TX/ETH_MII_TXD1/ETH_RMII_TXD1_129") (pintype "passive"))
    )
    (net (code "114") (name "/PG15") (class "Default")
      (node (ref "J3") (pin "8") (pinfunction "8_8") (pintype "passive"))
      (node (ref "U4") (pin "132") (pinfunction "PG15/U6_CTS/DCMI_D13_132") (pintype "passive"))
    )
    (net (code "115") (name "/RESET") (class "Default")
      (node (ref "C14") (pin "2") (pinfunction "2_2") (pintype "passive"))
      (node (ref "J1") (pin "15") (pinfunction "nSRST_15") (pintype "passive"))
      (node (ref "J6") (pin "6") (pinfunction "D0_6") (pintype "passive"))
      (node (ref "R24") (pin "1") (pinfunction "1_1") (pintype "passive"))
      (node (ref "RST") (pin "1") (pinfunction "C1_1") (pintype "passive"))
      (node (ref "U4") (pin "25") (pinfunction "NRST_25") (pintype "passive"))
    )
    (net (code "116") (name "/VBAT") (class "Default")
      (node (ref "C6") (pin "1") (pinfunction "1_1") (pintype "passive"))
      (node (ref "Q1") (pin "3") (pinfunction "3_3") (pintype "passive"))
      (node (ref "U4") (pin "6") (pinfunction "VBAT_6") (pintype "passive"))
    )
    (net (code "117") (name "/VREF+") (class "Default")
      (node (ref "C33") (pin "1") (pinfunction "1_1") (pintype "passive"))
      (node (ref "J2") (pin "56") (pinfunction "56_56") (pintype "passive"))
      (node (ref "R21") (pin "1") (pinfunction "1_1") (pintype "passive"))
      (node (ref "U4") (pin "32") (pinfunction "Vref+_32") (pintype "passive"))
    )
    (net (code "118") (name "3V3") (class "Default")
      (node (ref "C1") (pin "2") (pinfunction "2_2") (pintype "passive"))
      (node (ref "C13") (pin "2") (pinfunction "2_2") (pintype "passive"))
      (node (ref "C17") (pin "2") (pinfunction "2_2") (pintype "passive"))
      (node (ref "C18") (pin "2") (pinfunction "2_2") (pintype "passive"))
      (node (ref "C19") (pin "1") (pinfunction "1_1") (pintype "passive"))
      (node (ref "C2") (pin "1") (pinfunction "1_1") (pintype "passive"))
      (node (ref "C20") (pin "1") (pinfunction "1_1") (pintype "passive"))
      (node (ref "C21") (pin "1") (pinfunction "1_1") (pintype "passive"))
      (node (ref "C22") (pin "1") (pinfunction "1_1") (pintype "passive"))
      (node (ref "C23") (pin "1") (pinfunction "1_1") (pintype "passive"))
      (node (ref "C24") (pin "1") (pinfunction "1_1") (pintype "passive"))
      (node (ref "C25") (pin "1") (pinfunction "1_1") (pintype "passive"))
      (node (ref "C26") (pin "1") (pinfunction "1_1") (pintype "passive"))
      (node (ref "C27") (pin "1") (pinfunction "1_1") (pintype "passive"))
      (node (ref "C28") (pin "1") (pinfunction "1_1") (pintype "passive"))
      (node (ref "C29") (pin "1") (pinfunction "1_1") (pintype "passive"))
      (node (ref "C30") (pin "1") (pinfunction "1_1") (pintype "passive"))
      (node (ref "C31") (pin "1") (pinfunction "1_1") (pintype "passive"))
      (node (ref "C32") (pin "1") (pinfunction "1_1") (pintype "passive"))
      (node (ref "C39") (pin "1") (pinfunction "1_1") (pintype "passive"))
      (node (ref "C5") (pin "1") (pinfunction "1_1") (pintype "passive"))
      (node (ref "D1") (pin "1") (pinfunction "1_1") (pintype "passive"))
      (node (ref "D2") (pin "1") (pinfunction "1_1") (pintype "passive"))
      (node (ref "D3") (pin "1") (pinfunction "1_1") (pintype "passive"))
      (node (ref "J1") (pin "1") (pinfunction "Vref_1") (pintype "passive"))
      (node (ref "J1") (pin "2") (pinfunction "Vsupply_2") (pintype "passive"))
      (node (ref "J2") (pin "59") (pinfunction "59_59") (pintype "passive"))
      (node (ref "J2") (pin "60") (pinfunction "60_60") (pintype "passive"))
      (node (ref "J3") (pin "57") (pinfunction "57_57") (pintype "passive"))
      (node (ref "J6") (pin "23") (pinfunction "BL_23") (pintype "passive"))
      (node (ref "J6") (pin "26") (pinfunction "GND_26") (pintype "passive"))
      (node (ref "J8") (pin "2") (pinfunction "2_2") (pintype "passive"))
      (node (ref "Q1") (pin "2") (pinfunction "2_2") (pintype "passive"))
      (node (ref "R1") (pin "1") (pinfunction "1_1") (pintype "passive"))
      (node (ref "R2") (pin "1") (pinfunction "1_1") (pintype "passive"))
      (node (ref "R22") (pin "2") (pinfunction "2_2") (pintype "passive"))
      (node (ref "R24") (pin "2") (pinfunction "2_2") (pintype "passive"))
      (node (ref "R28") (pin "2") (pinfunction "2_2") (pintype "passive"))
      (node (ref "R29") (pin "2") (pinfunction "2_2") (pintype "passive"))
      (node (ref "R3") (pin "1") (pinfunction "1_1") (pintype "passive"))
      (node (ref "R30") (pin "2") (pinfunction "2_2") (pintype "passive"))
      (node (ref "R31") (pin "2") (pinfunction "2_2") (pintype "passive"))
      (node (ref "R32") (pin "2") (pinfunction "2_2") (pintype "passive"))
      (node (ref "R33") (pin "2") (pinfunction "2_2") (pintype "passive"))
      (node (ref "R34") (pin "2") (pinfunction "2_2") (pintype "passive"))
      (node (ref "R35") (pin "2") (pinfunction "2_2") (pintype "passive"))
      (node (ref "R4") (pin "1") (pinfunction "1_1") (pintype "passive"))
      (node (ref "R8") (pin "2") (pinfunction "2_2") (pintype "passive"))
      (node (ref "U1") (pin "2") (pinfunction "OUT_2") (pintype "passive"))
      (node (ref "U2") (pin "11") (pinfunction "VDD_11") (pintype "passive"))
      (node (ref "U2") (pin "33") (pinfunction "VDD_33") (pintype "passive"))
      (node (ref "U3") (pin "3") (pinfunction "WP_3") (pintype "passive"))
      (node (ref "U3") (pin "7") (pinfunction "HOLD_7") (pintype "passive"))
      (node (ref "U3") (pin "8") (pinfunction "VCC_8") (pintype "passive"))
      (node (ref "U4") (pin "108") (pinfunction "VDD_108") (pintype "passive"))
      (node (ref "U4") (pin "121") (pinfunction "VDD_121") (pintype "passive"))
      (node (ref "U4") (pin "131") (pinfunction "VDD_131") (pintype "passive"))
      (node (ref "U4") (pin "144") (pinfunction "VDD_144") (pintype "passive"))
      (node (ref "U4") (pin "17") (pinfunction "VDD_17") (pintype "passive"))
      (node (ref "U4") (pin "30") (pinfunction "VDD_30") (pintype "passive"))
      (node (ref "U4") (pin "39") (pinfunction "VDD_39") (pintype "passive"))
      (node (ref "U4") (pin "52") (pinfunction "VDD_52") (pintype "passive"))
      (node (ref "U4") (pin "62") (pinfunction "VDD_62") (pintype "passive"))
      (node (ref "U4") (pin "72") (pinfunction "VDD_72") (pintype "passive"))
      (node (ref "U4") (pin "84") (pinfunction "VDD_84") (pintype "passive"))
      (node (ref "U4") (pin "95") (pinfunction "VDD_95") (pintype "passive"))
      (node (ref "U5") (pin "4") (pinfunction "VCC_4") (pintype "passive"))
      (node (ref "WK_UP") (pin "1") (pinfunction "C1_1") (pintype "passive"))
    )
    (net (code "119") (name "5V") (class "Default")
      (node (ref "C3") (pin "1") (pinfunction "1_1") (pintype "passive"))
      (node (ref "C38") (pin "1") (pinfunction "1_1") (pintype "passive"))
      (node (ref "C4") (pin "1") (pinfunction "1_1") (pintype "passive"))
      (node (ref "J3") (pin "59") (pinfunction "59_59") (pintype "passive"))
      (node (ref "J5") (pin "1") (pinfunction "1_1") (pintype "passive"))
      (node (ref "J6") (pin "27") (pinfunction "GND_27") (pintype "passive"))
      (node (ref "R5") (pin "1") (pinfunction "1_1") (pintype "passive"))
      (node (ref "U1") (pin "3") (pinfunction "VCC_3") (pintype "passive"))
    )
    (net (code "120") (name "GND") (class "Default")
      (node (ref "B1") (pin "2") (pinfunction "-_2") (pintype "passive"))
      (node (ref "C1") (pin "1") (pinfunction "1_1") (pintype "passive"))
      (node (ref "C10") (pin "2") (pinfunction "2_2") (pintype "passive"))
      (node (ref "C11") (pin "2") (pinfunction "2_2") (pintype "passive"))
      (node (ref "C12") (pin "2") (pinfunction "2_2") (pintype "passive"))
      (node (ref "C13") (pin "1") (pinfunction "1_1") (pintype "passive"))
      (node (ref "C14") (pin "1") (pinfunction "1_1") (pintype "passive"))
      (node (ref "C15") (pin "1") (pinfunction "1_1") (pintype "passive"))
      (node (ref "C16") (pin "1") (pinfunction "1_1") (pintype "passive"))
      (node (ref "C17") (pin "1") (pinfunction "1_1") (pintype "passive"))
      (node (ref "C18") (pin "1") (pinfunction "1_1") (pintype "passive"))
      (node (ref "C19") (pin "2") (pinfunction "2_2") (pintype "passive"))
      (node (ref "C2") (pin "2") (pinfunction "2_2") (pintype "passive"))
      (node (ref "C20") (pin "2") (pinfunction "2_2") (pintype "passive"))
      (node (ref "C21") (pin "2") (pinfunction "2_2") (pintype "passive"))
      (node (ref "C22") (pin "2") (pinfunction "2_2") (pintype "passive"))
      (node (ref "C23") (pin "2") (pinfunction "2_2") (pintype "passive"))
      (node (ref "C24") (pin "2") (pinfunction "2_2") (pintype "passive"))
      (node (ref "C25") (pin "2") (pinfunction "2_2") (pintype "passive"))
      (node (ref "C26") (pin "2") (pinfunction "2_2") (pintype "passive"))
      (node (ref "C27") (pin "2") (pinfunction "2_2") (pintype "passive"))
      (node (ref "C28") (pin "2") (pinfunction "2_2") (pintype "passive"))
      (node (ref "C29") (pin "2") (pinfunction "2_2") (pintype "passive"))
      (node (ref "C3") (pin "2") (pinfunction "2_2") (pintype "passive"))
      (node (ref "C30") (pin "2") (pinfunction "2_2") (pintype "passive"))
      (node (ref "C31") (pin "2") (pinfunction "2_2") (pintype "passive"))
      (node (ref "C32") (pin "2") (pinfunction "2_2") (pintype "passive"))
      (node (ref "C33") (pin "2") (pinfunction "2_2") (pintype "passive"))
      (node (ref "C38") (pin "2") (pinfunction "2_2") (pintype "passive"))
      (node (ref "C39") (pin "2") (pinfunction "2_2") (pintype "passive"))
      (node (ref "C4") (pin "2") (pinfunction "2_2") (pintype "passive"))
      (node (ref "C5") (pin "2") (pinfunction "2_2") (pintype "passive"))
      (node (ref "C6") (pin "2") (pinfunction "2_2") (pintype "passive"))
      (node (ref "C7") (pin "1") (pinfunction "1_1") (pintype "passive"))
      (node (ref "C8") (pin "1") (pinfunction "1_1") (pintype "passive"))
      (node (ref "C9") (pin "2") (pinfunction "2_2") (pintype "passive"))
      (node (ref "J1") (pin "10") (pinfunction "GND_10") (pintype "passive"))
      (node (ref "J1") (pin "12") (pinfunction "GND_12") (pintype "passive"))
      (node (ref "J1") (pin "14") (pinfunction "GND_14") (pintype "passive"))
      (node (ref "J1") (pin "16") (pinfunction "GND_16") (pintype "passive"))
      (node (ref "J1") (pin "18") (pinfunction "GND_18") (pintype "passive"))
      (node (ref "J1") (pin "20") (pinfunction "GND_20") (pintype "passive"))
      (node (ref "J1") (pin "4") (pinfunction "GND_4") (pintype "passive"))
      (node (ref "J1") (pin "6") (pinfunction "GND_6") (pintype "passive"))
      (node (ref "J1") (pin "8") (pinfunction "GND_8") (pintype "passive"))
      (node (ref "J2") (pin "55") (pinfunction "55_55") (pintype "passive"))
      (node (ref "J3") (pin "58") (pinfunction "58_58") (pintype "passive"))
      (node (ref "J3") (pin "60") (pinfunction "60_60") (pintype "passive"))
      (node (ref "J4") (pin "5") (pinfunction "GND_5") (pintype "passive"))
      (node (ref "J5") (pin "2") (pinfunction "2_2") (pintype "passive"))
      (node (ref "J6") (pin "21") (pinfunction "D15_21") (pintype "passive"))
      (node (ref "J6") (pin "25") (pinfunction "VDD3.3_25") (pintype "passive"))
      (node (ref "J6") (pin "28") (pinfunction "BL_VDD_28") (pintype "passive"))
      (node (ref "J8") (pin "1") (pinfunction "1_1") (pintype "passive"))
      (node (ref "K0") (pin "1") (pinfunction "C1_1") (pintype "passive"))
      (node (ref "K1") (pin "1") (pinfunction "C1_1") (pintype "passive"))
      (node (ref "R12") (pin "2") (pinfunction "2_2") (pintype "passive"))
      (node (ref "R19") (pin "2") (pinfunction "2_2") (pintype "passive"))
      (node (ref "R25") (pin "2") (pinfunction "2_2") (pintype "passive"))
      (node (ref "R26") (pin "2") (pinfunction "2_2") (pintype "passive"))
      (node (ref "R9") (pin "1") (pinfunction "1_1") (pintype "passive"))
      (node (ref "RST") (pin "2") (pinfunction "C2_2") (pintype "passive"))
      (node (ref "U1") (pin "1") (pinfunction "GND_1") (pintype "passive"))
      (node (ref "U2") (pin "12") (pinfunction "GND_12") (pintype "passive"))
      (node (ref "U2") (pin "34") (pinfunction "GND_34") (pintype "passive"))
      (node (ref "U3") (pin "4") (pinfunction "GND_4") (pintype "passive"))
      (node (ref "U4") (pin "107") (pinfunction "VSS_107") (pintype "passive"))
      (node (ref "U4") (pin "120") (pinfunction "VSS_120") (pintype "passive"))
      (node (ref "U4") (pin "130") (pinfunction "VSS_130") (pintype "passive"))
      (node (ref "U4") (pin "16") (pinfunction "VSS_16") (pintype "passive"))
      (node (ref "U4") (pin "31") (pinfunction "VSSA_31") (pintype "passive"))
      (node (ref "U4") (pin "38") (pinfunction "VSS_38") (pintype "passive"))
      (node (ref "U4") (pin "51") (pinfunction "VSS_51") (pintype "passive"))
      (node (ref "U4") (pin "61") (pinfunction "VSS_61") (pintype "passive"))
      (node (ref "U4") (pin "83") (pinfunction "VSS_83") (pintype "passive"))
      (node (ref "U4") (pin "94") (pinfunction "VSS_94") (pintype "passive"))
      (node (ref "U5") (pin "6") (pinfunction "GND_6") (pintype "passive"))
      (node (ref "U5") (pin "9") (pinfunction "NC_9") (pintype "passive"))
    )
    (net (code "121") (name "Net-(B1-+)") (class "Default")
      (node (ref "B1") (pin "1") (pinfunction "+_1") (pintype "passive"))
      (node (ref "Q1") (pin "1") (pinfunction "1_1") (pintype "passive"))
    )
    (net (code "122") (name "Net-(D1-Pad2)") (class "Default")
      (node (ref "D1") (pin "2") (pinfunction "2_2") (pintype "passive"))
      (node (ref "R14") (pin "1") (pinfunction "1_1") (pintype "passive"))
    )
    (net (code "123") (name "Net-(D2-Pad2)") (class "Default")
      (node (ref "D2") (pin "2") (pinfunction "2_2") (pintype "passive"))
      (node (ref "R16") (pin "1") (pinfunction "1_1") (pintype "passive"))
    )
    (net (code "124") (name "Net-(D3-Pad2)") (class "Default")
      (node (ref "D3") (pin "2") (pinfunction "2_2") (pintype "passive"))
      (node (ref "R19") (pin "1") (pinfunction "1_1") (pintype "passive"))
    )
    (net (code "125") (name "Net-(J2-Pad57)") (class "Default")
      (node (ref "J2") (pin "57") (pinfunction "57_57") (pintype "passive"))
      (node (ref "R10") (pin "1") (pinfunction "1_1") (pintype "passive"))
    )
    (net (code "126") (name "Net-(J4-D+)") (class "Default")
      (node (ref "J4") (pin "3") (pinfunction "D+_3") (pintype "passive"))
      (node (ref "R7") (pin "1") (pinfunction "1_1") (pintype "passive"))
      (node (ref "R8") (pin "1") (pinfunction "1_1") (pintype "passive"))
    )
    (net (code "127") (name "Net-(J4-D-)") (class "Default")
      (node (ref "J4") (pin "2") (pinfunction "D-_2") (pintype "passive"))
      (node (ref "R6") (pin "1") (pinfunction "1_1") (pintype "passive"))
    )
    (net (code "128") (name "Net-(J4-VDD)") (class "Default")
      (node (ref "J4") (pin "1") (pinfunction "VDD_1") (pintype "passive"))
      (node (ref "R5") (pin "2") (pinfunction "2_2") (pintype "passive"))
    )
    (net (code "129") (name "Net-(U4-PDR_ON)") (class "Default")
      (node (ref "R26") (pin "1") (pinfunction "1_1") (pintype "passive"))
      (node (ref "R28") (pin "1") (pinfunction "1_1") (pintype "passive"))
      (node (ref "U4") (pin "143") (pinfunction "PDR_ON_143") (pintype "passive"))
    )
    (net (code "130") (name "Net-(U4-PH0-OSC_IN)") (class "Default")
      (node (ref "C10") (pin "1") (pinfunction "1_1") (pintype "passive"))
      (node (ref "R20") (pin "1") (pinfunction "1_1") (pintype "passive"))
      (node (ref "U4") (pin "23") (pinfunction "PH0-OSC_IN_23") (pintype "passive"))
      (node (ref "Y2") (pin "1") (pinfunction "1_1") (pintype "passive"))
    )
    (net (code "131") (name "Net-(U4-PH1-OSC_OUT)") (class "Default")
      (node (ref "C9") (pin "1") (pinfunction "1_1") (pintype "passive"))
      (node (ref "R20") (pin "2") (pinfunction "2_2") (pintype "passive"))
      (node (ref "U4") (pin "24") (pinfunction "PH1-OSC_OUT_24") (pintype "passive"))
      (node (ref "Y2") (pin "2") (pinfunction "2_2") (pintype "passive"))
    )
    (net (code "132") (name "Net-(U4-Vcap_1)") (class "Default")
      (node (ref "C11") (pin "1") (pinfunction "1_1") (pintype "passive"))
      (node (ref "U4") (pin "71") (pinfunction "Vcap_1_71") (pintype "passive"))
    )
    (net (code "133") (name "Net-(U4-Vcap_2)") (class "Default")
      (node (ref "C12") (pin "1") (pinfunction "1_1") (pintype "passive"))
      (node (ref "U4") (pin "106") (pinfunction "Vcap_2_106") (pintype "passive"))
    )
    (net (code "134") (name "VDDA") (class "Default")
      (node (ref "C15") (pin "2") (pinfunction "2_2") (pintype "passive"))
      (node (ref "C16") (pin "2") (pinfunction "2_2") (pintype "passive"))
      (node (ref "R21") (pin "2") (pinfunction "2_2") (pintype "passive"))
      (node (ref "R22") (pin "1") (pinfunction "1_1") (pintype "passive"))
      (node (ref "U4") (pin "33") (pinfunction "VDDA_33") (pintype "passive"))
    )
    (net (code "135") (name "unconnected-(J1-NC-Pad17)") (class "Default")
      (node (ref "J1") (pin "17") (pinfunction "NC_17") (pintype "passive"))
    )
    (net (code "136") (name "unconnected-(J1-NC-Pad19)") (class "Default")
      (node (ref "J1") (pin "19") (pinfunction "NC_19") (pintype "passive"))
    )
    (net (code "137") (name "unconnected-(J1-RTCK-Pad11)") (class "Default")
      (node (ref "J1") (pin "11") (pinfunction "RTCK_11") (pintype "passive"))
    )
    (net (code "138") (name "unconnected-(J4-NCC-Pad4)") (class "Default")
      (node (ref "J4") (pin "4") (pinfunction "NCC_4") (pintype "passive"))
    )
    (net (code "139") (name "unconnected-(J6-T_PEN-Pad31)") (class "Default")
      (node (ref "J6") (pin "31") (pinfunction "T_PEN_31") (pintype "passive"))
    )
  )
)
